# prototype.net
KiCad netlist of a schematic drawn in EAGLE
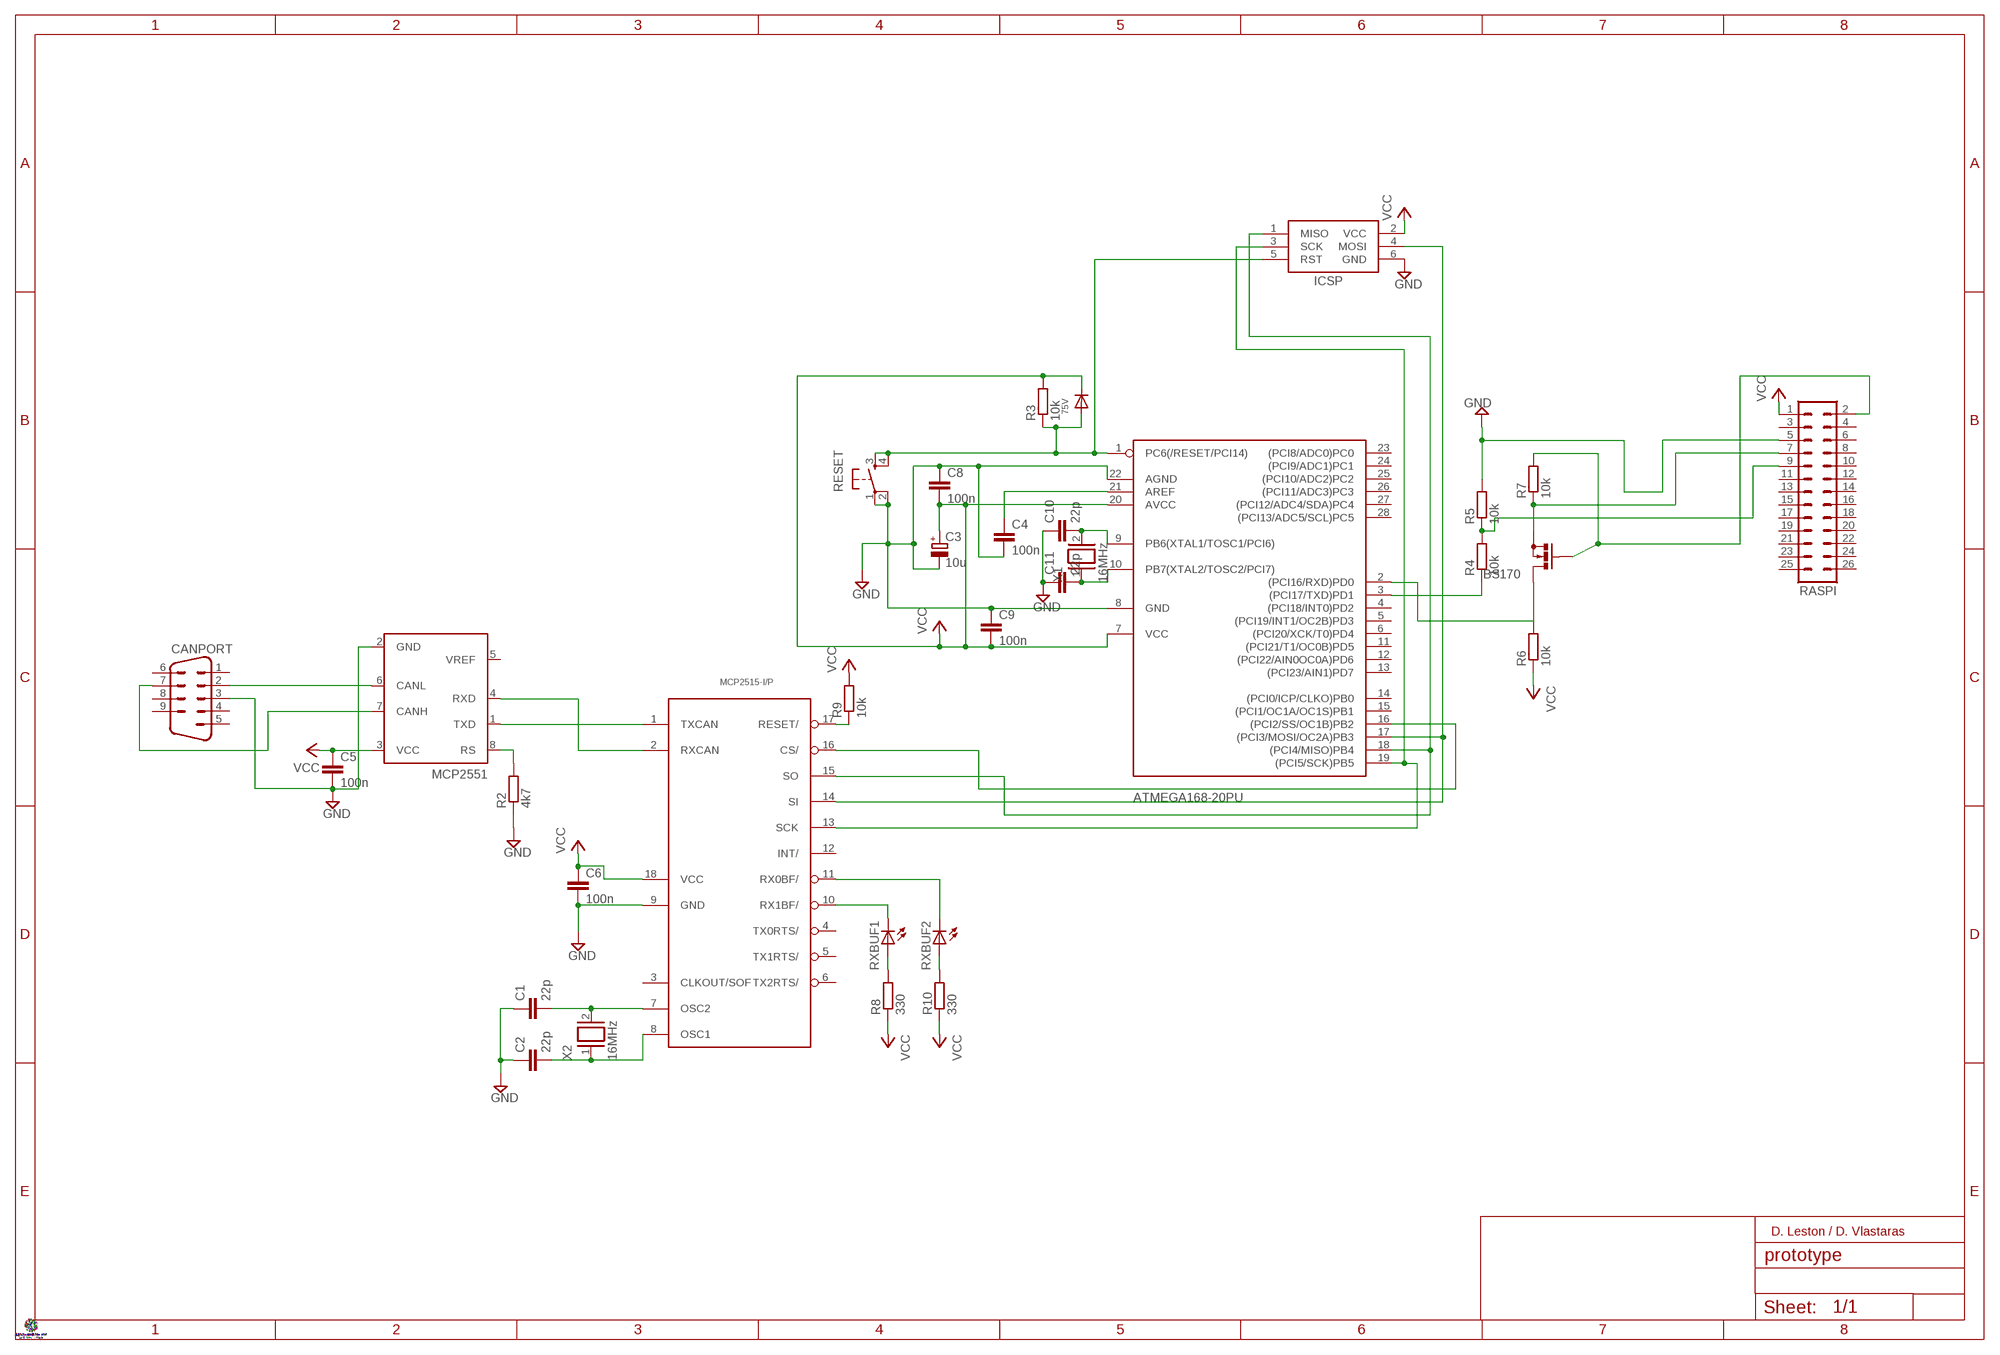
[diagram p0: schematic, sheet 1]

(export (version "E")
  (design (tool "Eeschema 10.0.6"))
  (components
    (comp (ref "75V")
      (value "DIODEDO-1N4148")
      (footprint "eagle-import:DO-1N4148")
      (libsource (lib "eagle-import") (part "DIODEDO-1N4148"))
    )
    (comp (ref "ATMEGA168-20PU")
      (value "ATMEGA168V-10P")
      (footprint "eagle-import:DIL28-3")
      (libsource (lib "eagle-import") (part "ATMEGA168PV-10"))
    )
    (comp (ref "BS170")
      (value "BS170")
      (footprint "eagle-import:SOT54E")
      (libsource (lib "eagle-import") (part "BS170"))
    )
    (comp (ref "C1")
      (value "22p")
      (footprint "eagle-import:C050-025X075")
      (libsource (lib "eagle-import") (part "C-EU050-025X075"))
    )
    (comp (ref "C2")
      (value "22p")
      (footprint "eagle-import:C050-025X075")
      (libsource (lib "eagle-import") (part "C-EU050-025X075"))
    )
    (comp (ref "C3")
      (value "10u")
      (footprint "eagle-import:E2-5")
      (libsource (lib "eagle-import") (part "CPOL-EUE2-5"))
    )
    (comp (ref "C4")
      (value "100n")
      (footprint "eagle-import:C050-025X075")
      (libsource (lib "eagle-import") (part "C-EU050-025X075"))
    )
    (comp (ref "C5")
      (value "100n")
      (footprint "eagle-import:C050-025X075")
      (libsource (lib "eagle-import") (part "C-EU050-025X075"))
    )
    (comp (ref "C6")
      (value "100n")
      (footprint "eagle-import:C050-025X075")
      (libsource (lib "eagle-import") (part "C-EU050-025X075"))
    )
    (comp (ref "C8")
      (value "100n")
      (footprint "eagle-import:C050-025X075")
      (libsource (lib "eagle-import") (part "C-EU050-025X075"))
    )
    (comp (ref "C9")
      (value "100n")
      (footprint "eagle-import:C050-025X075")
      (libsource (lib "eagle-import") (part "C-EU050-025X075"))
    )
    (comp (ref "C10")
      (value "22p")
      (footprint "eagle-import:C050-025X075")
      (libsource (lib "eagle-import") (part "C-EU050-025X075"))
    )
    (comp (ref "C11")
      (value "22p")
      (footprint "eagle-import:C050-025X075")
      (libsource (lib "eagle-import") (part "C-EU050-025X075"))
    )
    (comp (ref "CANPORT")
      (value "M09VP")
      (footprint "eagle-import:M09VP")
      (libsource (lib "eagle-import") (part "M09VP"))
    )
    (comp (ref "ICSP")
      (value "AVRISP-6")
      (footprint "eagle-import:AVRISP")
      (libsource (lib "eagle-import") (part "AVRISP-6"))
    )
    (comp (ref "MCP2515-I/P")
      (value "MCP2515DIL")
      (footprint "eagle-import:DIL18")
      (libsource (lib "eagle-import") (part "MCP2515DIL"))
    )
    (comp (ref "MCP2551")
      (value "PCA82C250")
      (footprint "eagle-import:DIL08")
      (libsource (lib "eagle-import") (part "PCA82C250"))
    )
    (comp (ref "R2")
      (value "4k7")
      (footprint "eagle-import:0204_7")
      (libsource (lib "eagle-import") (part "R-EU_0204/7"))
    )
    (comp (ref "R3")
      (value "10k")
      (footprint "eagle-import:0204_7")
      (libsource (lib "eagle-import") (part "R-EU_0204/7"))
    )
    (comp (ref "R4")
      (value "10k")
      (footprint "eagle-import:0204_7")
      (libsource (lib "eagle-import") (part "R-EU_0204/7"))
    )
    (comp (ref "R5")
      (value "10k")
      (footprint "eagle-import:0204_7")
      (libsource (lib "eagle-import") (part "R-EU_0204/7"))
    )
    (comp (ref "R6")
      (value "10k")
      (footprint "eagle-import:0204_7")
      (libsource (lib "eagle-import") (part "R-EU_0204/7"))
    )
    (comp (ref "R7")
      (value "10k")
      (footprint "eagle-import:0204_7")
      (libsource (lib "eagle-import") (part "R-EU_0204/7"))
    )
    (comp (ref "R8")
      (value "330")
      (footprint "eagle-import:0204_7")
      (libsource (lib "eagle-import") (part "R-EU_0204/7"))
    )
    (comp (ref "R9")
      (value "10k")
      (footprint "eagle-import:0204_7")
      (libsource (lib "eagle-import") (part "R-EU_0204/7"))
    )
    (comp (ref "R10")
      (value "330")
      (footprint "eagle-import:0204_7")
      (libsource (lib "eagle-import") (part "R-EU_0204/7"))
    )
    (comp (ref "RASPI")
      (value "MA13-2")
      (footprint "eagle-import:MA13-2")
      (libsource (lib "eagle-import") (part "MA13-2"))
    )
    (comp (ref "RESET")
      (value "DTS-6")
      (footprint "eagle-import:DTS-6")
      (libsource (lib "eagle-import") (part "DTS-6"))
    )
    (comp (ref "RXBUF1")
      (value "LED5MM")
      (footprint "eagle-import:LED5MM")
      (libsource (lib "eagle-import") (part "LED5MM"))
    )
    (comp (ref "RXBUF2")
      (value "LED5MM")
      (footprint "eagle-import:LED5MM")
      (libsource (lib "eagle-import") (part "LED5MM"))
    )
    (comp (ref "X1")
      (value "16MHz")
      (footprint "eagle-import:QS")
      (libsource (lib "eagle-import") (part "XTAL/S"))
    )
    (comp (ref "X2")
      (value "16MHz")
      (footprint "eagle-import:QS")
      (libsource (lib "eagle-import") (part "XTAL/S"))
    )
  )
  (nets
    (net (code "1") (name "GND") (class "Default")
      (node (ref "ATMEGA168-20PU") (pin "22") (pinfunction "AGND_22") (pintype "bidirectional"))
      (node (ref "ATMEGA168-20PU") (pin "8") (pinfunction "GND_8") (pintype "bidirectional"))
      (node (ref "C1") (pin "1") (pinfunction "1_1") (pintype "passive"))
      (node (ref "C10") (pin "1") (pinfunction "1_1") (pintype "passive"))
      (node (ref "C11") (pin "1") (pinfunction "1_1") (pintype "passive"))
      (node (ref "C2") (pin "1") (pinfunction "1_1") (pintype "passive"))
      (node (ref "C3") (pin "-") (pinfunction "-_-") (pintype "passive"))
      (node (ref "C4") (pin "2") (pinfunction "2_2") (pintype "passive"))
      (node (ref "C5") (pin "2") (pinfunction "2_2") (pintype "passive"))
      (node (ref "C6") (pin "2") (pinfunction "2_2") (pintype "passive"))
      (node (ref "C8") (pin "1") (pinfunction "1_1") (pintype "passive"))
      (node (ref "C9") (pin "1") (pinfunction "1_1") (pintype "passive"))
      (node (ref "CANPORT") (pin "3") (pinfunction "3_3") (pintype "passive"))
      (node (ref "ICSP") (pin "6") (pinfunction "GND_6") (pintype "power_in"))
      (node (ref "MCP2515-I/P") (pin "9") (pinfunction "GND_9") (pintype "power_in"))
      (node (ref "MCP2551") (pin "2") (pinfunction "GND_2") (pintype "power_in"))
      (node (ref "R2") (pin "1") (pinfunction "1_1") (pintype "passive"))
      (node (ref "R5") (pin "2") (pinfunction "2_2") (pintype "passive"))
      (node (ref "RASPI") (pin "5") (pinfunction "5_5") (pintype "passive"))
      (node (ref "RESET") (pin "1") (pinfunction "1_1") (pintype "passive"))
      (node (ref "RESET") (pin "2") (pinfunction "2_2") (pintype "passive"))
    )
    (net (code "2") (name "Net-(ATMEGA168-20PU-(PCI2{slash}SS{slash}OC1B)PB2)") (class "Default")
      (node (ref "ATMEGA168-20PU") (pin "16") (pinfunction "(PCI2/SS/OC1B)PB2_16") (pintype "bidirectional"))
      (node (ref "MCP2515-I/P") (pin "16") (pinfunction "CS/_16") (pintype "input"))
    )
    (net (code "3") (name "Net-(ATMEGA168-20PU-(PCI3{slash}MOSI{slash}OC2A)PB3)") (class "Default")
      (node (ref "ATMEGA168-20PU") (pin "17") (pinfunction "(PCI3/MOSI/OC2A)PB3_17") (pintype "bidirectional"))
      (node (ref "ICSP") (pin "4") (pinfunction "MOSI_4") (pintype "output"))
      (node (ref "MCP2515-I/P") (pin "14") (pinfunction "SI_14") (pintype "input"))
    )
    (net (code "4") (name "Net-(ATMEGA168-20PU-(PCI4{slash}MISO)PB4)") (class "Default")
      (node (ref "ATMEGA168-20PU") (pin "18") (pinfunction "(PCI4/MISO)PB4_18") (pintype "bidirectional"))
      (node (ref "ICSP") (pin "1") (pinfunction "MISO_1") (pintype "input"))
      (node (ref "MCP2515-I/P") (pin "15") (pinfunction "SO_15") (pintype "output"))
    )
    (net (code "5") (name "Net-(ATMEGA168-20PU-(PCI5{slash}SCK)PB5)") (class "Default")
      (node (ref "ATMEGA168-20PU") (pin "19") (pinfunction "(PCI5/SCK)PB5_19") (pintype "bidirectional"))
      (node (ref "ICSP") (pin "3") (pinfunction "SCK_3") (pintype "output"))
      (node (ref "MCP2515-I/P") (pin "13") (pinfunction "SCK_13") (pintype "input"))
    )
    (net (code "6") (name "Net-(ATMEGA168-20PU-(PCI16{slash}RXD)PD0)") (class "Default")
      (node (ref "ATMEGA168-20PU") (pin "2") (pinfunction "(PCI16/RXD)PD0_2") (pintype "bidirectional"))
      (node (ref "BS170") (pin "D") (pinfunction "D_D") (pintype "passive"))
      (node (ref "R6") (pin "2") (pinfunction "2_2") (pintype "passive"))
    )
    (net (code "7") (name "Net-(ATMEGA168-20PU-(PCI17{slash}TXD)PD1)") (class "Default")
      (node (ref "ATMEGA168-20PU") (pin "3") (pinfunction "(PCI17/TXD)PD1_3") (pintype "bidirectional"))
      (node (ref "R4") (pin "1") (pinfunction "1_1") (pintype "passive"))
    )
    (net (code "8") (name "Net-(ATMEGA168-20PU-AREF)") (class "Default")
      (node (ref "ATMEGA168-20PU") (pin "21") (pinfunction "AREF_21") (pintype "bidirectional"))
      (node (ref "C4") (pin "1") (pinfunction "1_1") (pintype "passive"))
    )
    (net (code "9") (name "Net-(ATMEGA168-20PU-PB6(XTAL1{slash}TOSC1{slash}PCI6))") (class "Default")
      (node (ref "ATMEGA168-20PU") (pin "9") (pinfunction "PB6(XTAL1/TOSC1/PCI6)_9") (pintype "bidirectional"))
      (node (ref "C10") (pin "2") (pinfunction "2_2") (pintype "passive"))
      (node (ref "X1") (pin "2") (pinfunction "2_2") (pintype "passive"))
    )
    (net (code "10") (name "Net-(ATMEGA168-20PU-PB7(XTAL2{slash}TOSC2{slash}PCI7))") (class "Default")
      (node (ref "ATMEGA168-20PU") (pin "10") (pinfunction "PB7(XTAL2/TOSC2/PCI7)_10") (pintype "bidirectional"))
      (node (ref "C11") (pin "2") (pinfunction "2_2") (pintype "passive"))
      (node (ref "X1") (pin "1") (pinfunction "1_1") (pintype "passive"))
    )
    (net (code "11") (name "Net-(ATMEGA168-20PU-PC6({slash}RESET{slash}PCI14))") (class "Default")
      (node (ref "75V") (pin "A") (pinfunction "A_A") (pintype "passive"))
      (node (ref "ATMEGA168-20PU") (pin "1") (pinfunction "PC6(/RESET/PCI14)_1") (pintype "bidirectional"))
      (node (ref "ICSP") (pin "5") (pinfunction "RST_5") (pintype "output"))
      (node (ref "R3") (pin "1") (pinfunction "1_1") (pintype "passive"))
      (node (ref "RESET") (pin "3") (pinfunction "3_3") (pintype "passive"))
      (node (ref "RESET") (pin "4") (pinfunction "4_4") (pintype "passive"))
    )
    (net (code "12") (name "Net-(BS170-PadG)") (class "Default")
      (node (ref "BS170") (pin "G") (pinfunction "G_G") (pintype "passive"))
      (node (ref "R7") (pin "2") (pinfunction "2_2") (pintype "passive"))
      (node (ref "RASPI") (pin "2") (pinfunction "2_2") (pintype "passive"))
    )
    (net (code "13") (name "Net-(BS170-PadS)") (class "Default")
      (node (ref "BS170") (pin "S") (pinfunction "S_S") (pintype "passive"))
      (node (ref "R7") (pin "1") (pinfunction "1_1") (pintype "passive"))
      (node (ref "RASPI") (pin "7") (pinfunction "7_7") (pintype "passive"))
    )
    (net (code "14") (name "Net-(MCP2515-I/P-OSC1)") (class "Default")
      (node (ref "C2") (pin "2") (pinfunction "2_2") (pintype "passive"))
      (node (ref "MCP2515-I/P") (pin "8") (pinfunction "OSC1_8") (pintype "bidirectional"))
      (node (ref "X2") (pin "1") (pinfunction "1_1") (pintype "passive"))
    )
    (net (code "15") (name "Net-(MCP2515-I/P-OSC2)") (class "Default")
      (node (ref "C1") (pin "2") (pinfunction "2_2") (pintype "passive"))
      (node (ref "MCP2515-I/P") (pin "7") (pinfunction "OSC2_7") (pintype "bidirectional"))
      (node (ref "X2") (pin "2") (pinfunction "2_2") (pintype "passive"))
    )
    (net (code "16") (name "Net-(MCP2515-I/P-RESET{slash})") (class "Default")
      (node (ref "MCP2515-I/P") (pin "17") (pinfunction "RESET/_17") (pintype "input"))
      (node (ref "R9") (pin "1") (pinfunction "1_1") (pintype "passive"))
    )
    (net (code "17") (name "Net-(MCP2515-I/P-RX0BF{slash})") (class "Default")
      (node (ref "MCP2515-I/P") (pin "11") (pinfunction "RX0BF/_11") (pintype "bidirectional"))
      (node (ref "RXBUF2") (pin "K") (pinfunction "C_K") (pintype "passive"))
    )
    (net (code "18") (name "Net-(MCP2515-I/P-RX1BF{slash})") (class "Default")
      (node (ref "MCP2515-I/P") (pin "10") (pinfunction "RX1BF/_10") (pintype "bidirectional"))
      (node (ref "RXBUF1") (pin "K") (pinfunction "C_K") (pintype "passive"))
    )
    (net (code "19") (name "Net-(MCP2515-I/P-RXCAN)") (class "Default")
      (node (ref "MCP2515-I/P") (pin "2") (pinfunction "RXCAN_2") (pintype "input"))
      (node (ref "MCP2551") (pin "4") (pinfunction "RXD_4") (pintype "output"))
    )
    (net (code "20") (name "Net-(MCP2515-I/P-TXCAN)") (class "Default")
      (node (ref "MCP2515-I/P") (pin "1") (pinfunction "TXCAN_1") (pintype "output"))
      (node (ref "MCP2551") (pin "1") (pinfunction "TXD_1") (pintype "input"))
    )
    (net (code "21") (name "Net-(MCP2551-CANH)") (class "Default")
      (node (ref "CANPORT") (pin "7") (pinfunction "7_7") (pintype "passive"))
      (node (ref "MCP2551") (pin "7") (pinfunction "CANH_7") (pintype "bidirectional"))
    )
    (net (code "22") (name "Net-(MCP2551-CANL)") (class "Default")
      (node (ref "CANPORT") (pin "2") (pinfunction "2_2") (pintype "passive"))
      (node (ref "MCP2551") (pin "6") (pinfunction "CANL_6") (pintype "bidirectional"))
    )
    (net (code "23") (name "Net-(MCP2551-RS)") (class "Default")
      (node (ref "MCP2551") (pin "8") (pinfunction "RS_8") (pintype "input"))
      (node (ref "R2") (pin "2") (pinfunction "2_2") (pintype "passive"))
    )
    (net (code "24") (name "Net-(R4-Pad2)") (class "Default")
      (node (ref "R4") (pin "2") (pinfunction "2_2") (pintype "passive"))
      (node (ref "R5") (pin "1") (pinfunction "1_1") (pintype "passive"))
      (node (ref "RASPI") (pin "9") (pinfunction "9_9") (pintype "passive"))
    )
    (net (code "25") (name "Net-(R8-Pad2)") (class "Default")
      (node (ref "R8") (pin "2") (pinfunction "2_2") (pintype "passive"))
      (node (ref "RXBUF1") (pin "A") (pinfunction "A_A") (pintype "passive"))
    )
    (net (code "26") (name "Net-(R10-Pad2)") (class "Default")
      (node (ref "R10") (pin "2") (pinfunction "2_2") (pintype "passive"))
      (node (ref "RXBUF2") (pin "A") (pinfunction "A_A") (pintype "passive"))
    )
    (net (code "27") (name "VCC") (class "Default")
      (node (ref "75V") (pin "C") (pinfunction "C_C") (pintype "passive"))
      (node (ref "ATMEGA168-20PU") (pin "20") (pinfunction "AVCC_20") (pintype "bidirectional"))
      (node (ref "ATMEGA168-20PU") (pin "7") (pinfunction "VCC_7") (pintype "bidirectional"))
      (node (ref "C3") (pin "+") (pinfunction "+_+") (pintype "passive"))
      (node (ref "C5") (pin "1") (pinfunction "1_1") (pintype "passive"))
      (node (ref "C6") (pin "1") (pinfunction "1_1") (pintype "passive"))
      (node (ref "C8") (pin "2") (pinfunction "2_2") (pintype "passive"))
      (node (ref "C9") (pin "2") (pinfunction "2_2") (pintype "passive"))
      (node (ref "ICSP") (pin "2") (pinfunction "VCC_2") (pintype "power_in"))
      (node (ref "MCP2515-I/P") (pin "18") (pinfunction "VCC_18") (pintype "power_in"))
      (node (ref "MCP2551") (pin "3") (pinfunction "VCC_3") (pintype "power_in"))
      (node (ref "R10") (pin "1") (pinfunction "1_1") (pintype "passive"))
      (node (ref "R3") (pin "2") (pinfunction "2_2") (pintype "passive"))
      (node (ref "R6") (pin "1") (pinfunction "1_1") (pintype "passive"))
      (node (ref "R8") (pin "1") (pinfunction "1_1") (pintype "passive"))
      (node (ref "R9") (pin "2") (pinfunction "2_2") (pintype "passive"))
      (node (ref "RASPI") (pin "1") (pinfunction "1_1") (pintype "passive"))
    )
    (net (code "28") (name "unconnected-(ATMEGA168-20PU-(PCI0{slash}ICP{slash}CLKO)PB0-Pad14)") (class "Default")
      (node (ref "ATMEGA168-20PU") (pin "14") (pinfunction "(PCI0/ICP/CLKO)PB0_14") (pintype "bidirectional"))
    )
    (net (code "29") (name "unconnected-(ATMEGA168-20PU-(PCI1{slash}OC1A{slash}OC1S)PB1-Pad15)") (class "Default")
      (node (ref "ATMEGA168-20PU") (pin "15") (pinfunction "(PCI1/OC1A/OC1S)PB1_15") (pintype "bidirectional"))
    )
    (net (code "30") (name "unconnected-(ATMEGA168-20PU-(PCI8{slash}ADC0)PC0-Pad23)") (class "Default")
      (node (ref "ATMEGA168-20PU") (pin "23") (pinfunction "(PCI8/ADC0)PC0_23") (pintype "bidirectional"))
    )
    (net (code "31") (name "unconnected-(ATMEGA168-20PU-(PCI9{slash}ADC1)PC1-Pad24)") (class "Default")
      (node (ref "ATMEGA168-20PU") (pin "24") (pinfunction "(PCI9/ADC1)PC1_24") (pintype "bidirectional"))
    )
    (net (code "32") (name "unconnected-(ATMEGA168-20PU-(PCI10{slash}ADC2)PC2-Pad25)") (class "Default")
      (node (ref "ATMEGA168-20PU") (pin "25") (pinfunction "(PCI10/ADC2)PC2_25") (pintype "bidirectional"))
    )
    (net (code "33") (name "unconnected-(ATMEGA168-20PU-(PCI11{slash}ADC3)PC3-Pad26)") (class "Default")
      (node (ref "ATMEGA168-20PU") (pin "26") (pinfunction "(PCI11/ADC3)PC3_26") (pintype "bidirectional"))
    )
    (net (code "34") (name "unconnected-(ATMEGA168-20PU-(PCI12{slash}ADC4{slash}SDA)PC4-Pad27)") (class "Default")
      (node (ref "ATMEGA168-20PU") (pin "27") (pinfunction "(PCI12/ADC4/SDA)PC4_27") (pintype "bidirectional"))
    )
    (net (code "35") (name "unconnected-(ATMEGA168-20PU-(PCI13{slash}ADC5{slash}SCL)PC5-Pad28)") (class "Default")
      (node (ref "ATMEGA168-20PU") (pin "28") (pinfunction "(PCI13/ADC5/SCL)PC5_28") (pintype "bidirectional"))
    )
    (net (code "36") (name "unconnected-(ATMEGA168-20PU-(PCI18{slash}INT0)PD2-Pad4)") (class "Default")
      (node (ref "ATMEGA168-20PU") (pin "4") (pinfunction "(PCI18/INT0)PD2_4") (pintype "bidirectional"))
    )
    (net (code "37") (name "unconnected-(ATMEGA168-20PU-(PCI19{slash}INT1{slash}OC2B)PD3-Pad5)") (class "Default")
      (node (ref "ATMEGA168-20PU") (pin "5") (pinfunction "(PCI19/INT1/OC2B)PD3_5") (pintype "bidirectional"))
    )
    (net (code "38") (name "unconnected-(ATMEGA168-20PU-(PCI20{slash}XCK{slash}T0)PD4-Pad6)") (class "Default")
      (node (ref "ATMEGA168-20PU") (pin "6") (pinfunction "(PCI20/XCK/T0)PD4_6") (pintype "bidirectional"))
    )
    (net (code "39") (name "unconnected-(ATMEGA168-20PU-(PCI21{slash}T1{slash}OC0B)PD5-Pad11)") (class "Default")
      (node (ref "ATMEGA168-20PU") (pin "11") (pinfunction "(PCI21/T1/OC0B)PD5_11") (pintype "bidirectional"))
    )
    (net (code "40") (name "unconnected-(ATMEGA168-20PU-(PCI22{slash}AIN0OC0A)PD6-Pad12)") (class "Default")
      (node (ref "ATMEGA168-20PU") (pin "12") (pinfunction "(PCI22/AIN0OC0A)PD6_12") (pintype "bidirectional"))
    )
    (net (code "41") (name "unconnected-(ATMEGA168-20PU-(PCI23{slash}AIN1)PD7-Pad13)") (class "Default")
      (node (ref "ATMEGA168-20PU") (pin "13") (pinfunction "(PCI23/AIN1)PD7_13") (pintype "bidirectional"))
    )
    (net (code "42") (name "unconnected-(CANPORT-Pad1)") (class "Default")
      (node (ref "CANPORT") (pin "1") (pinfunction "1_1") (pintype "passive"))
    )
    (net (code "43") (name "unconnected-(CANPORT-Pad4)") (class "Default")
      (node (ref "CANPORT") (pin "4") (pinfunction "4_4") (pintype "passive"))
    )
    (net (code "44") (name "unconnected-(CANPORT-Pad5)") (class "Default")
      (node (ref "CANPORT") (pin "5") (pinfunction "5_5") (pintype "passive"))
    )
    (net (code "45") (name "unconnected-(CANPORT-Pad6)") (class "Default")
      (node (ref "CANPORT") (pin "6") (pinfunction "6_6") (pintype "passive"))
    )
    (net (code "46") (name "unconnected-(CANPORT-Pad8)") (class "Default")
      (node (ref "CANPORT") (pin "8") (pinfunction "8_8") (pintype "passive"))
    )
    (net (code "47") (name "unconnected-(CANPORT-Pad9)") (class "Default")
      (node (ref "CANPORT") (pin "9") (pinfunction "9_9") (pintype "passive"))
    )
    (net (code "48") (name "unconnected-(MCP2515-I/P-CLKOUT{slash}SOF-Pad3)") (class "Default")
      (node (ref "MCP2515-I/P") (pin "3") (pinfunction "CLKOUT/SOF_3") (pintype "bidirectional"))
    )
    (net (code "49") (name "unconnected-(MCP2515-I/P-INT{slash}-Pad12)") (class "Default")
      (node (ref "MCP2515-I/P") (pin "12") (pinfunction "INT/_12") (pintype "output"))
    )
    (net (code "50") (name "unconnected-(MCP2515-I/P-TX0RTS{slash}-Pad4)") (class "Default")
      (node (ref "MCP2515-I/P") (pin "4") (pinfunction "TX0RTS/_4") (pintype "bidirectional"))
    )
    (net (code "51") (name "unconnected-(MCP2515-I/P-TX1RTS{slash}-Pad5)") (class "Default")
      (node (ref "MCP2515-I/P") (pin "5") (pinfunction "TX1RTS/_5") (pintype "bidirectional"))
    )
    (net (code "52") (name "unconnected-(MCP2515-I/P-TX2RTS{slash}-Pad6)") (class "Default")
      (node (ref "MCP2515-I/P") (pin "6") (pinfunction "TX2RTS/_6") (pintype "bidirectional"))
    )
    (net (code "53") (name "unconnected-(MCP2551-VREF-Pad5)") (class "Default")
      (node (ref "MCP2551") (pin "5") (pinfunction "VREF_5") (pintype "output"))
    )
    (net (code "54") (name "unconnected-(RASPI-Pad3)") (class "Default")
      (node (ref "RASPI") (pin "3") (pinfunction "3_3") (pintype "passive"))
    )
    (net (code "55") (name "unconnected-(RASPI-Pad4)") (class "Default")
      (node (ref "RASPI") (pin "4") (pinfunction "4_4") (pintype "passive"))
    )
    (net (code "56") (name "unconnected-(RASPI-Pad6)") (class "Default")
      (node (ref "RASPI") (pin "6") (pinfunction "6_6") (pintype "passive"))
    )
    (net (code "57") (name "unconnected-(RASPI-Pad8)") (class "Default")
      (node (ref "RASPI") (pin "8") (pinfunction "8_8") (pintype "passive"))
    )
    (net (code "58") (name "unconnected-(RASPI-Pad10)") (class "Default")
      (node (ref "RASPI") (pin "10") (pinfunction "10_10") (pintype "passive"))
    )
    (net (code "59") (name "unconnected-(RASPI-Pad11)") (class "Default")
      (node (ref "RASPI") (pin "11") (pinfunction "11_11") (pintype "passive"))
    )
    (net (code "60") (name "unconnected-(RASPI-Pad12)") (class "Default")
      (node (ref "RASPI") (pin "12") (pinfunction "12_12") (pintype "passive"))
    )
    (net (code "61") (name "unconnected-(RASPI-Pad13)") (class "Default")
      (node (ref "RASPI") (pin "13") (pinfunction "13_13") (pintype "passive"))
    )
    (net (code "62") (name "unconnected-(RASPI-Pad14)") (class "Default")
      (node (ref "RASPI") (pin "14") (pinfunction "14_14") (pintype "passive"))
    )
    (net (code "63") (name "unconnected-(RASPI-Pad15)") (class "Default")
      (node (ref "RASPI") (pin "15") (pinfunction "15_15") (pintype "passive"))
    )
    (net (code "64") (name "unconnected-(RASPI-Pad16)") (class "Default")
      (node (ref "RASPI") (pin "16") (pinfunction "16_16") (pintype "passive"))
    )
    (net (code "65") (name "unconnected-(RASPI-Pad17)") (class "Default")
      (node (ref "RASPI") (pin "17") (pinfunction "17_17") (pintype "passive"))
    )
    (net (code "66") (name "unconnected-(RASPI-Pad18)") (class "Default")
      (node (ref "RASPI") (pin "18") (pinfunction "18_18") (pintype "passive"))
    )
    (net (code "67") (name "unconnected-(RASPI-Pad19)") (class "Default")
      (node (ref "RASPI") (pin "19") (pinfunction "19_19") (pintype "passive"))
    )
    (net (code "68") (name "unconnected-(RASPI-Pad20)") (class "Default")
      (node (ref "RASPI") (pin "20") (pinfunction "20_20") (pintype "passive"))
    )
    (net (code "69") (name "unconnected-(RASPI-Pad21)") (class "Default")
      (node (ref "RASPI") (pin "21") (pinfunction "21_21") (pintype "passive"))
    )
    (net (code "70") (name "unconnected-(RASPI-Pad22)") (class "Default")
      (node (ref "RASPI") (pin "22") (pinfunction "22_22") (pintype "passive"))
    )
    (net (code "71") (name "unconnected-(RASPI-Pad23)") (class "Default")
      (node (ref "RASPI") (pin "23") (pinfunction "23_23") (pintype "passive"))
    )
    (net (code "72") (name "unconnected-(RASPI-Pad24)") (class "Default")
      (node (ref "RASPI") (pin "24") (pinfunction "24_24") (pintype "passive"))
    )
    (net (code "73") (name "unconnected-(RASPI-Pad25)") (class "Default")
      (node (ref "RASPI") (pin "25") (pinfunction "25_25") (pintype "passive"))
    )
    (net (code "74") (name "unconnected-(RASPI-Pad26)") (class "Default")
      (node (ref "RASPI") (pin "26") (pinfunction "26_26") (pintype "passive"))
    )
  )
)
